# medusa-ai-audio.net
KiCad netlist of a schematic drawn in Altium Designer
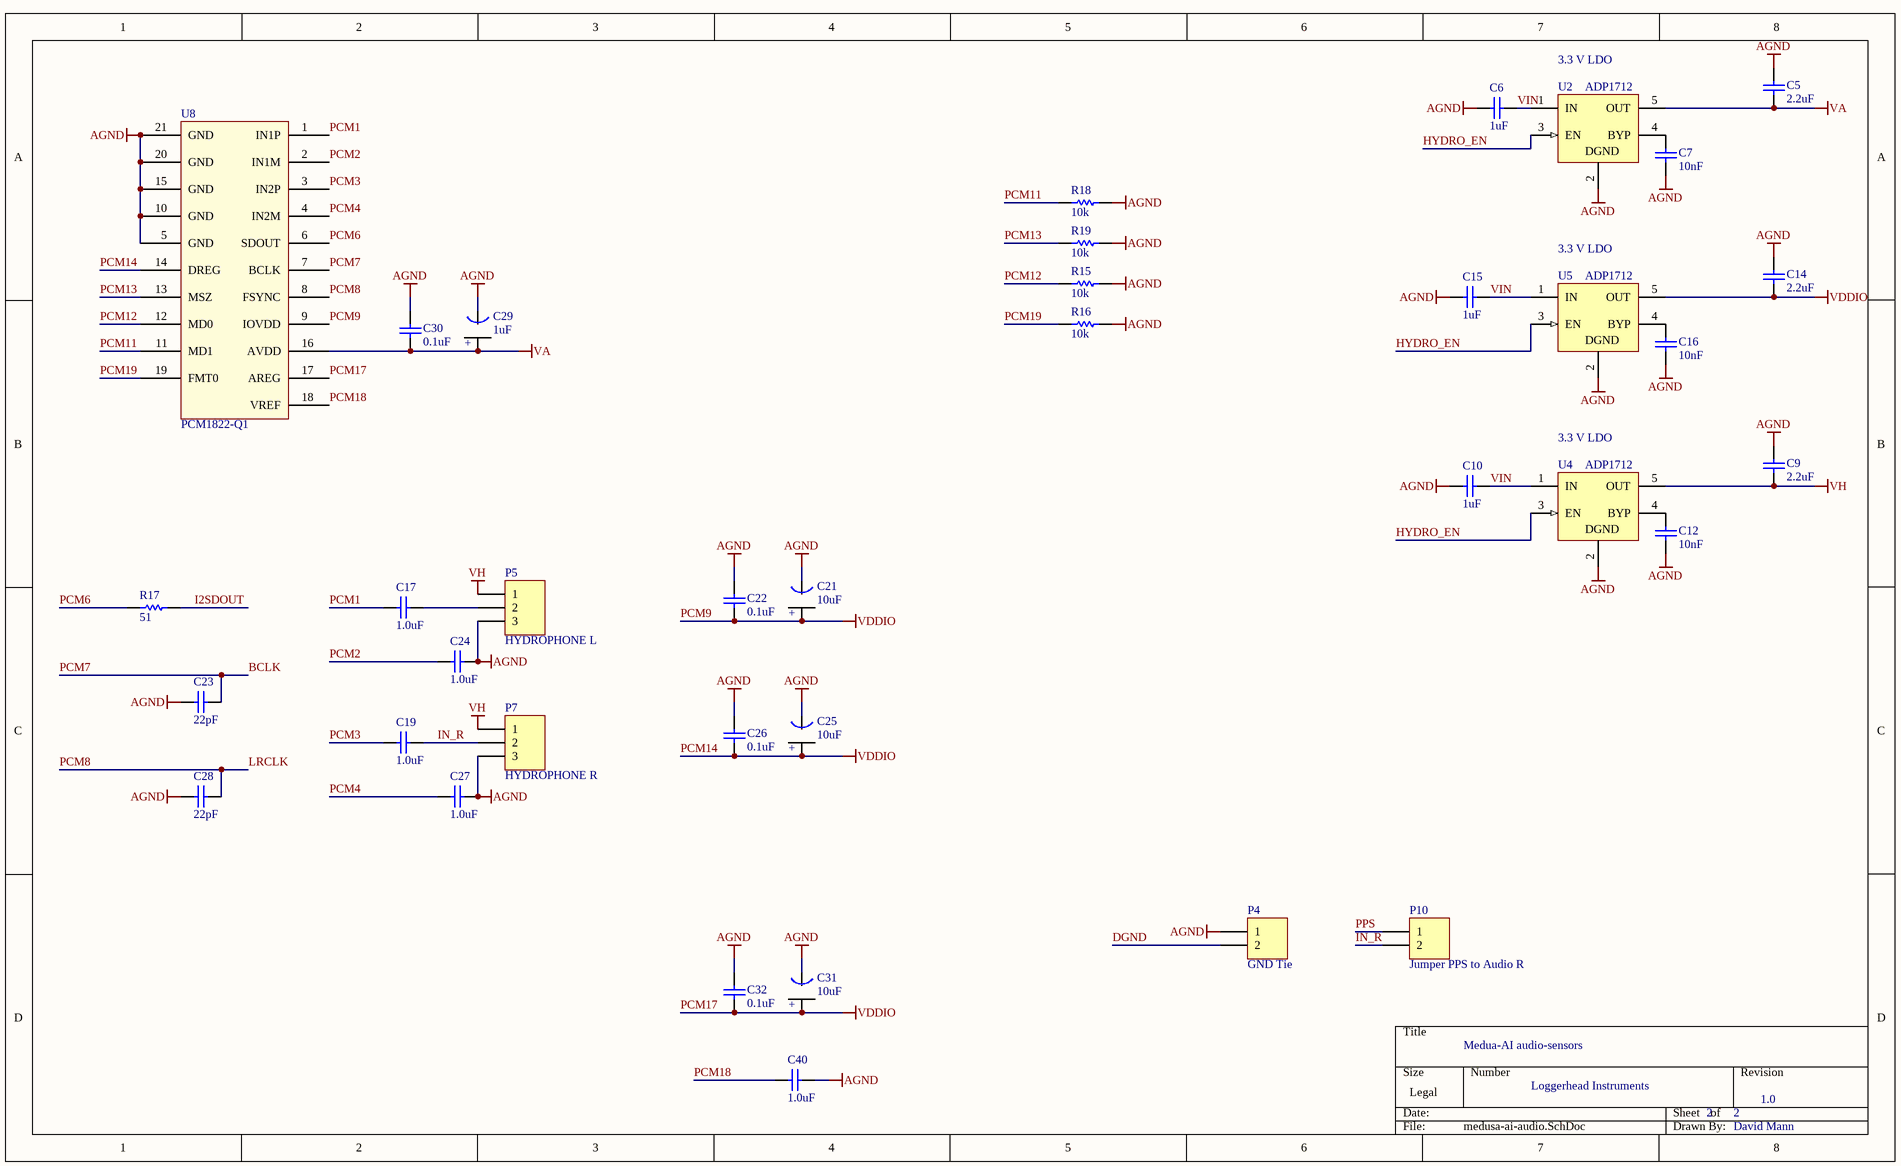
[diagram p0: medusa-ai-audio.SchDoc]

(export (version "E")
  (design (tool "Eeschema 10.0.6"))
  (components
    (comp (ref "C5")
      (value "2.2uF")
      (footprint "0402")
      (description "Ceramic Chip Capacitor - Standard")
      (fields (field (name "PUBLISHER") "Altium Limited"))
      (libsource (lib "KEMET Chip Capacitor") (part "C0402"))
    )
    (comp (ref "C6")
      (value "1uF")
      (footprint "0402")
      (description "Ceramic Chip Capacitor - Standard")
      (fields (field (name "PUBLISHER") "Altium Limited"))
      (libsource (lib "KEMET Chip Capacitor") (part "C0402"))
    )
    (comp (ref "C7")
      (value "10nF")
      (footprint "0402")
      (description "Ceramic Chip Capacitor - Standard")
      (fields (field (name "PUBLISHER") "Altium Limited"))
      (libsource (lib "KEMET Chip Capacitor") (part "C0402"))
    )
    (comp (ref "C9")
      (value "2.2uF")
      (footprint "0402")
      (description "Ceramic Chip Capacitor - Standard")
      (fields (field (name "PUBLISHER") "Altium Limited"))
      (libsource (lib "KEMET Chip Capacitor") (part "C0402"))
    )
    (comp (ref "C10")
      (value "1uF")
      (footprint "0402")
      (description "Ceramic Chip Capacitor - Standard")
      (fields (field (name "PUBLISHER") "Altium Limited"))
      (libsource (lib "KEMET Chip Capacitor") (part "C0402"))
    )
    (comp (ref "C12")
      (value "10nF")
      (footprint "0402")
      (description "Ceramic Chip Capacitor - Standard")
      (fields (field (name "PUBLISHER") "Altium Limited"))
      (libsource (lib "KEMET Chip Capacitor") (part "C0402"))
    )
    (comp (ref "C14")
      (value "2.2uF")
      (footprint "0402")
      (description "Ceramic Chip Capacitor - Standard")
      (fields (field (name "PUBLISHER") "Altium Limited"))
      (libsource (lib "KEMET Chip Capacitor") (part "C0402"))
    )
    (comp (ref "C15")
      (value "1uF")
      (footprint "0402")
      (description "Ceramic Chip Capacitor - Standard")
      (fields (field (name "PUBLISHER") "Altium Limited"))
      (libsource (lib "KEMET Chip Capacitor") (part "C0402"))
    )
    (comp (ref "C16")
      (value "10nF")
      (footprint "0402")
      (description "Ceramic Chip Capacitor - Standard")
      (fields (field (name "PUBLISHER") "Altium Limited"))
      (libsource (lib "KEMET Chip Capacitor") (part "C0402"))
    )
    (comp (ref "C17")
      (value "1.0uF")
      (footprint "0402")
      (description "Ceramic Chip Capacitor - Standard")
      (fields (field (name "PUBLISHER") "Altium Limited"))
      (libsource (lib "KEMET Chip Capacitor") (part "C0402"))
    )
    (comp (ref "C19")
      (value "1.0uF")
      (footprint "0402")
      (description "Ceramic Chip Capacitor - Standard")
      (fields (field (name "PUBLISHER") "Altium Limited"))
      (libsource (lib "KEMET Chip Capacitor") (part "C0402"))
    )
    (comp (ref "C21") (value "10uF") (footprint "Tant0805") (libsource (lib "Loggerhead") (part "Tant0805")))
    (comp (ref "C22")
      (value "0.1uF")
      (footprint "0402")
      (description "Ceramic Chip Capacitor - Standard")
      (fields (field (name "PUBLISHER") "Altium Limited"))
      (libsource (lib "KEMET Chip Capacitor") (part "C0402"))
    )
    (comp (ref "C23")
      (value "22pF")
      (footprint "0402")
      (description "Ceramic Chip Capacitor - Standard")
      (fields (field (name "PUBLISHER") "Altium Limited"))
      (libsource (lib "KEMET Chip Capacitor") (part "C0402"))
    )
    (comp (ref "C24")
      (value "1.0uF")
      (footprint "0402")
      (description "Ceramic Chip Capacitor - Standard")
      (fields (field (name "PUBLISHER") "Altium Limited"))
      (libsource (lib "KEMET Chip Capacitor") (part "C0402"))
    )
    (comp (ref "C25") (value "10uF") (footprint "Tant0805") (libsource (lib "Loggerhead") (part "Tant0805")))
    (comp (ref "C26")
      (value "0.1uF")
      (footprint "0402")
      (description "Ceramic Chip Capacitor - Standard")
      (fields (field (name "PUBLISHER") "Altium Limited"))
      (libsource (lib "KEMET Chip Capacitor") (part "C0402"))
    )
    (comp (ref "C27")
      (value "1.0uF")
      (footprint "0402")
      (description "Ceramic Chip Capacitor - Standard")
      (fields (field (name "PUBLISHER") "Altium Limited"))
      (libsource (lib "KEMET Chip Capacitor") (part "C0402"))
    )
    (comp (ref "C28")
      (value "22pF")
      (footprint "0402")
      (description "Ceramic Chip Capacitor - Standard")
      (fields (field (name "PUBLISHER") "Altium Limited"))
      (libsource (lib "KEMET Chip Capacitor") (part "C0402"))
    )
    (comp (ref "C29") (value "1uF") (footprint "Tant0805") (libsource (lib "Loggerhead") (part "Tant0805")))
    (comp (ref "C30")
      (value "0.1uF")
      (footprint "0402")
      (description "Ceramic Chip Capacitor - Standard")
      (fields (field (name "PUBLISHER") "Altium Limited"))
      (libsource (lib "KEMET Chip Capacitor") (part "C0402"))
    )
    (comp (ref "C31") (value "10uF") (footprint "Tant0805") (libsource (lib "Loggerhead") (part "Tant0805")))
    (comp (ref "C32")
      (value "0.1uF")
      (footprint "0402")
      (description "Ceramic Chip Capacitor - Standard")
      (fields (field (name "PUBLISHER") "Altium Limited"))
      (libsource (lib "KEMET Chip Capacitor") (part "C0402"))
    )
    (comp (ref "C40")
      (value "1.0uF")
      (footprint "0402")
      (description "Ceramic Chip Capacitor - Standard")
      (fields (field (name "PUBLISHER") "Altium Limited"))
      (libsource (lib "KEMET Chip Capacitor") (part "C0402"))
    )
    (comp (ref "P4")
      (value "GND Tie")
      (footprint "HDR1X2")
      (description "Header, 2-Pin")
      (fields (field (name "PUBLISHER") "Altium Limited"))
      (libsource (lib "Miscellaneous Connectors") (part "Header 2"))
    )
    (comp (ref "P5")
      (value "HYDROPHONE L")
      (footprint "HDR1X3")
      (description "Header, 3-Pin")
      (fields (field (name "PUBLISHER") "Altium Limited"))
      (libsource (lib "Miscellaneous Connectors") (part "Header 3"))
    )
    (comp (ref "P7")
      (value "HYDROPHONE R")
      (footprint "HDR1X3")
      (description "Header, 3-Pin")
      (fields (field (name "PUBLISHER") "Altium Limited"))
      (libsource (lib "Miscellaneous Connectors") (part "Header 3"))
    )
    (comp (ref "P10")
      (value "Jumper PPS to Audio R")
      (footprint "HDR1X2")
      (description "Header, 2-Pin")
      (fields (field (name "PUBLISHER") "Altium Limited"))
      (libsource (lib "Miscellaneous Connectors") (part "Header 2"))
    )
    (comp (ref "R15")
      (value "10k")
      (footprint "3-0603")
      (fields (field (name "PUBLISHER") "Altium Limited"))
      (libsource (lib "Panasonic Resistor") (part "ERJ3RK"))
    )
    (comp (ref "R16")
      (value "10k")
      (footprint "3-0603")
      (fields (field (name "PUBLISHER") "Altium Limited"))
      (libsource (lib "Panasonic Resistor") (part "ERJ3RK"))
    )
    (comp (ref "R17")
      (value "51")
      (footprint "3-0603")
      (fields (field (name "PUBLISHER") "Altium Limited"))
      (libsource (lib "Panasonic Resistor") (part "ERJ3RK"))
    )
    (comp (ref "R18")
      (value "10k")
      (footprint "3-0603")
      (fields (field (name "PUBLISHER") "Altium Limited"))
      (libsource (lib "Panasonic Resistor") (part "ERJ3RK"))
    )
    (comp (ref "R19")
      (value "10k")
      (footprint "3-0603")
      (fields (field (name "PUBLISHER") "Altium Limited"))
      (libsource (lib "Panasonic Resistor") (part "ERJ3RK"))
    )
    (comp (ref "U2")
      (value "ADP1712")
      (footprint "MF05A_N")
      (description "Micropower, 150mA Low-Noise Ultra Low-Dropout CMOS Voltage Regulator")
      (fields
        (field (name "PARTNUMBER") "LP3985IM5-3.3")
        (field (name "MANUFACTURER") "National Semiconductor")
        (field (name "PUBLISHER") "Altium Limited")
      )
      (libsource (lib "NSC LDO") (part "LP3985IM5-3.3"))
    )
    (comp (ref "U4")
      (value "ADP1712")
      (footprint "MF05A_N")
      (description "Micropower, 150mA Low-Noise Ultra Low-Dropout CMOS Voltage Regulator")
      (fields
        (field (name "PARTNUMBER") "LP3985IM5-3.3")
        (field (name "MANUFACTURER") "National Semiconductor")
        (field (name "PUBLISHER") "Altium Limited")
      )
      (libsource (lib "NSC LDO") (part "LP3985IM5-3.3"))
    )
    (comp (ref "U5")
      (value "ADP1712")
      (footprint "MF05A_N")
      (description "Micropower, 150mA Low-Noise Ultra Low-Dropout CMOS Voltage Regulator")
      (fields
        (field (name "PARTNUMBER") "LP3985IM5-3.3")
        (field (name "MANUFACTURER") "National Semiconductor")
        (field (name "PUBLISHER") "Altium Limited")
      )
      (libsource (lib "NSC LDO") (part "LP3985IM5-3.3"))
    )
    (comp (ref "U8")
      (value "PCM1822-Q1")
      (footprint "PCM1822-Q1")
      (description "TI PCM1822-Q1 Stereo Channel, 32-Bit, 192-kHz, Burr-Brown Audio ADC")
      (libsource (lib "Loggerhead") (part "PCM1822-Q1"))
    )
  )
  (nets
    (net (code "1") (name "/BCLK") (class "Default")
      (node (ref "C23") (pin "2") (pinfunction "2_2") (pintype "passive"))
      (node (ref "U8") (pin "7") (pinfunction "BCLK_7") (pintype "passive"))
    )
    (net (code "2") (name "/DGND") (class "Default")
      (node (ref "P4") (pin "2") (pinfunction "2_2") (pintype "passive"))
    )
    (net (code "3") (name "/HYDRO_EN") (class "Default")
      (node (ref "U2") (pin "3") (pinfunction "EN_3") (pintype "input"))
      (node (ref "U4") (pin "3") (pinfunction "EN_3") (pintype "input"))
      (node (ref "U5") (pin "3") (pinfunction "EN_3") (pintype "input"))
    )
    (net (code "4") (name "/I2SDOUT") (class "Default")
      (node (ref "R17") (pin "2") (pinfunction "2_2") (pintype "passive"))
    )
    (net (code "5") (name "/IN_R") (class "Default")
      (node (ref "C19") (pin "1") (pinfunction "1_1") (pintype "passive"))
      (node (ref "P10") (pin "2") (pinfunction "2_2") (pintype "passive"))
      (node (ref "P7") (pin "2") (pinfunction "2_2") (pintype "passive"))
    )
    (net (code "6") (name "/LRCLK") (class "Default")
      (node (ref "C28") (pin "2") (pinfunction "2_2") (pintype "passive"))
      (node (ref "U8") (pin "8") (pinfunction "FSYNC_8") (pintype "passive"))
    )
    (net (code "7") (name "/PCM1") (class "Default")
      (node (ref "C17") (pin "2") (pinfunction "2_2") (pintype "passive"))
      (node (ref "U8") (pin "1") (pinfunction "IN1P_1") (pintype "passive"))
    )
    (net (code "8") (name "/PCM2") (class "Default")
      (node (ref "C24") (pin "2") (pinfunction "2_2") (pintype "passive"))
      (node (ref "U8") (pin "2") (pinfunction "IN1M_2") (pintype "passive"))
    )
    (net (code "9") (name "/PCM3") (class "Default")
      (node (ref "C19") (pin "2") (pinfunction "2_2") (pintype "passive"))
      (node (ref "U8") (pin "3") (pinfunction "IN2P_3") (pintype "passive"))
    )
    (net (code "10") (name "/PCM4") (class "Default")
      (node (ref "C27") (pin "2") (pinfunction "2_2") (pintype "passive"))
      (node (ref "U8") (pin "4") (pinfunction "IN2M_4") (pintype "passive"))
    )
    (net (code "11") (name "/PCM6") (class "Default")
      (node (ref "R17") (pin "1") (pinfunction "1_1") (pintype "passive"))
      (node (ref "U8") (pin "6") (pinfunction "SDOUT_6") (pintype "passive"))
    )
    (net (code "12") (name "/PCM11") (class "Default")
      (node (ref "R18") (pin "1") (pinfunction "1_1") (pintype "passive"))
      (node (ref "U8") (pin "11") (pinfunction "MD1_11") (pintype "passive"))
    )
    (net (code "13") (name "/PCM12") (class "Default")
      (node (ref "R15") (pin "1") (pinfunction "1_1") (pintype "passive"))
      (node (ref "U8") (pin "12") (pinfunction "MD0_12") (pintype "passive"))
    )
    (net (code "14") (name "/PCM13") (class "Default")
      (node (ref "R19") (pin "1") (pinfunction "1_1") (pintype "passive"))
      (node (ref "U8") (pin "13") (pinfunction "MSZ_13") (pintype "passive"))
    )
    (net (code "15") (name "/PCM18") (class "Default")
      (node (ref "C40") (pin "2") (pinfunction "2_2") (pintype "passive"))
      (node (ref "U8") (pin "18") (pinfunction "VREF_18") (pintype "passive"))
    )
    (net (code "16") (name "/PCM19") (class "Default")
      (node (ref "R16") (pin "1") (pinfunction "1_1") (pintype "passive"))
      (node (ref "U8") (pin "19") (pinfunction "FMT0_19") (pintype "passive"))
    )
    (net (code "17") (name "/PPS") (class "Default")
      (node (ref "P10") (pin "1") (pinfunction "1_1") (pintype "passive"))
    )
    (net (code "18") (name "/VIN") (class "Default")
      (node (ref "C10") (pin "1") (pinfunction "1_1") (pintype "passive"))
      (node (ref "C15") (pin "1") (pinfunction "1_1") (pintype "passive"))
      (node (ref "C6") (pin "1") (pinfunction "1_1") (pintype "passive"))
      (node (ref "U2") (pin "1") (pinfunction "IN_1") (pintype "power_in"))
      (node (ref "U4") (pin "1") (pinfunction "IN_1") (pintype "power_in"))
      (node (ref "U5") (pin "1") (pinfunction "IN_1") (pintype "power_in"))
    )
    (net (code "19") (name "AGND") (class "Default")
      (node (ref "C10") (pin "2") (pinfunction "2_2") (pintype "passive"))
      (node (ref "C12") (pin "2") (pinfunction "2_2") (pintype "passive"))
      (node (ref "C14") (pin "2") (pinfunction "2_2") (pintype "passive"))
      (node (ref "C15") (pin "2") (pinfunction "2_2") (pintype "passive"))
      (node (ref "C16") (pin "2") (pinfunction "2_2") (pintype "passive"))
      (node (ref "C21") (pin "1") (pinfunction "GND_1") (pintype "passive"))
      (node (ref "C22") (pin "1") (pinfunction "1_1") (pintype "passive"))
      (node (ref "C23") (pin "1") (pinfunction "1_1") (pintype "passive"))
      (node (ref "C24") (pin "1") (pinfunction "1_1") (pintype "passive"))
      (node (ref "C25") (pin "1") (pinfunction "GND_1") (pintype "passive"))
      (node (ref "C26") (pin "1") (pinfunction "1_1") (pintype "passive"))
      (node (ref "C27") (pin "1") (pinfunction "1_1") (pintype "passive"))
      (node (ref "C28") (pin "1") (pinfunction "1_1") (pintype "passive"))
      (node (ref "C29") (pin "1") (pinfunction "GND_1") (pintype "passive"))
      (node (ref "C30") (pin "1") (pinfunction "1_1") (pintype "passive"))
      (node (ref "C31") (pin "1") (pinfunction "GND_1") (pintype "passive"))
      (node (ref "C32") (pin "1") (pinfunction "1_1") (pintype "passive"))
      (node (ref "C40") (pin "1") (pinfunction "1_1") (pintype "passive"))
      (node (ref "C5") (pin "2") (pinfunction "2_2") (pintype "passive"))
      (node (ref "C6") (pin "2") (pinfunction "2_2") (pintype "passive"))
      (node (ref "C7") (pin "2") (pinfunction "2_2") (pintype "passive"))
      (node (ref "C9") (pin "2") (pinfunction "2_2") (pintype "passive"))
      (node (ref "P4") (pin "1") (pinfunction "1_1") (pintype "passive"))
      (node (ref "P5") (pin "3") (pinfunction "3_3") (pintype "passive"))
      (node (ref "P7") (pin "3") (pinfunction "3_3") (pintype "passive"))
      (node (ref "R15") (pin "2") (pinfunction "2_2") (pintype "passive"))
      (node (ref "R16") (pin "2") (pinfunction "2_2") (pintype "passive"))
      (node (ref "R18") (pin "2") (pinfunction "2_2") (pintype "passive"))
      (node (ref "R19") (pin "2") (pinfunction "2_2") (pintype "passive"))
      (node (ref "U2") (pin "2") (pinfunction "GND_2") (pintype "power_in"))
      (node (ref "U4") (pin "2") (pinfunction "GND_2") (pintype "power_in"))
      (node (ref "U5") (pin "2") (pinfunction "GND_2") (pintype "power_in"))
      (node (ref "U8") (pin "10") (pinfunction "GND_10") (pintype "passive"))
      (node (ref "U8") (pin "15") (pinfunction "GND_15") (pintype "passive"))
      (node (ref "U8") (pin "20") (pinfunction "GND_20") (pintype "passive"))
      (node (ref "U8") (pin "21") (pinfunction "GND_21") (pintype "passive"))
      (node (ref "U8") (pin "5") (pinfunction "GND_5") (pintype "passive"))
    )
    (net (code "20") (name "Net-(C17-Pad1)") (class "Default")
      (node (ref "C17") (pin "1") (pinfunction "1_1") (pintype "passive"))
      (node (ref "P5") (pin "2") (pinfunction "2_2") (pintype "passive"))
    )
    (net (code "21") (name "Net-(U2-BYP)") (class "Default")
      (node (ref "C7") (pin "1") (pinfunction "1_1") (pintype "passive"))
      (node (ref "U2") (pin "4") (pinfunction "BYP_4") (pintype "passive"))
    )
    (net (code "22") (name "Net-(U4-BYP)") (class "Default")
      (node (ref "C12") (pin "1") (pinfunction "1_1") (pintype "passive"))
      (node (ref "U4") (pin "4") (pinfunction "BYP_4") (pintype "passive"))
    )
    (net (code "23") (name "Net-(U5-BYP)") (class "Default")
      (node (ref "C16") (pin "1") (pinfunction "1_1") (pintype "passive"))
      (node (ref "U5") (pin "4") (pinfunction "BYP_4") (pintype "passive"))
    )
    (net (code "24") (name "VA") (class "Default")
      (node (ref "C29") (pin "2") (pinfunction "+_2") (pintype "passive"))
      (node (ref "C30") (pin "2") (pinfunction "2_2") (pintype "passive"))
      (node (ref "C5") (pin "1") (pinfunction "1_1") (pintype "passive"))
      (node (ref "U2") (pin "5") (pinfunction "OUT_5") (pintype "power_in"))
      (node (ref "U8") (pin "16") (pinfunction "AVDD_16") (pintype "passive"))
    )
    (net (code "25") (name "VDDIO") (class "Default")
      (node (ref "C14") (pin "1") (pinfunction "1_1") (pintype "passive"))
      (node (ref "C21") (pin "2") (pinfunction "+_2") (pintype "passive"))
      (node (ref "C22") (pin "2") (pinfunction "2_2") (pintype "passive"))
      (node (ref "C25") (pin "2") (pinfunction "+_2") (pintype "passive"))
      (node (ref "C26") (pin "2") (pinfunction "2_2") (pintype "passive"))
      (node (ref "C31") (pin "2") (pinfunction "+_2") (pintype "passive"))
      (node (ref "C32") (pin "2") (pinfunction "2_2") (pintype "passive"))
      (node (ref "U5") (pin "5") (pinfunction "OUT_5") (pintype "power_in"))
      (node (ref "U8") (pin "14") (pinfunction "DREG_14") (pintype "passive"))
      (node (ref "U8") (pin "17") (pinfunction "AREG_17") (pintype "passive"))
      (node (ref "U8") (pin "9") (pinfunction "IOVDD_9") (pintype "passive"))
    )
    (net (code "26") (name "VH") (class "Default")
      (node (ref "C9") (pin "1") (pinfunction "1_1") (pintype "passive"))
      (node (ref "P5") (pin "1") (pinfunction "1_1") (pintype "passive"))
      (node (ref "P7") (pin "1") (pinfunction "1_1") (pintype "passive"))
      (node (ref "U4") (pin "5") (pinfunction "OUT_5") (pintype "power_in"))
    )
  )
)
